# 1__STLU01.net
KiCad netlist of a schematic drawn in Altium Designer
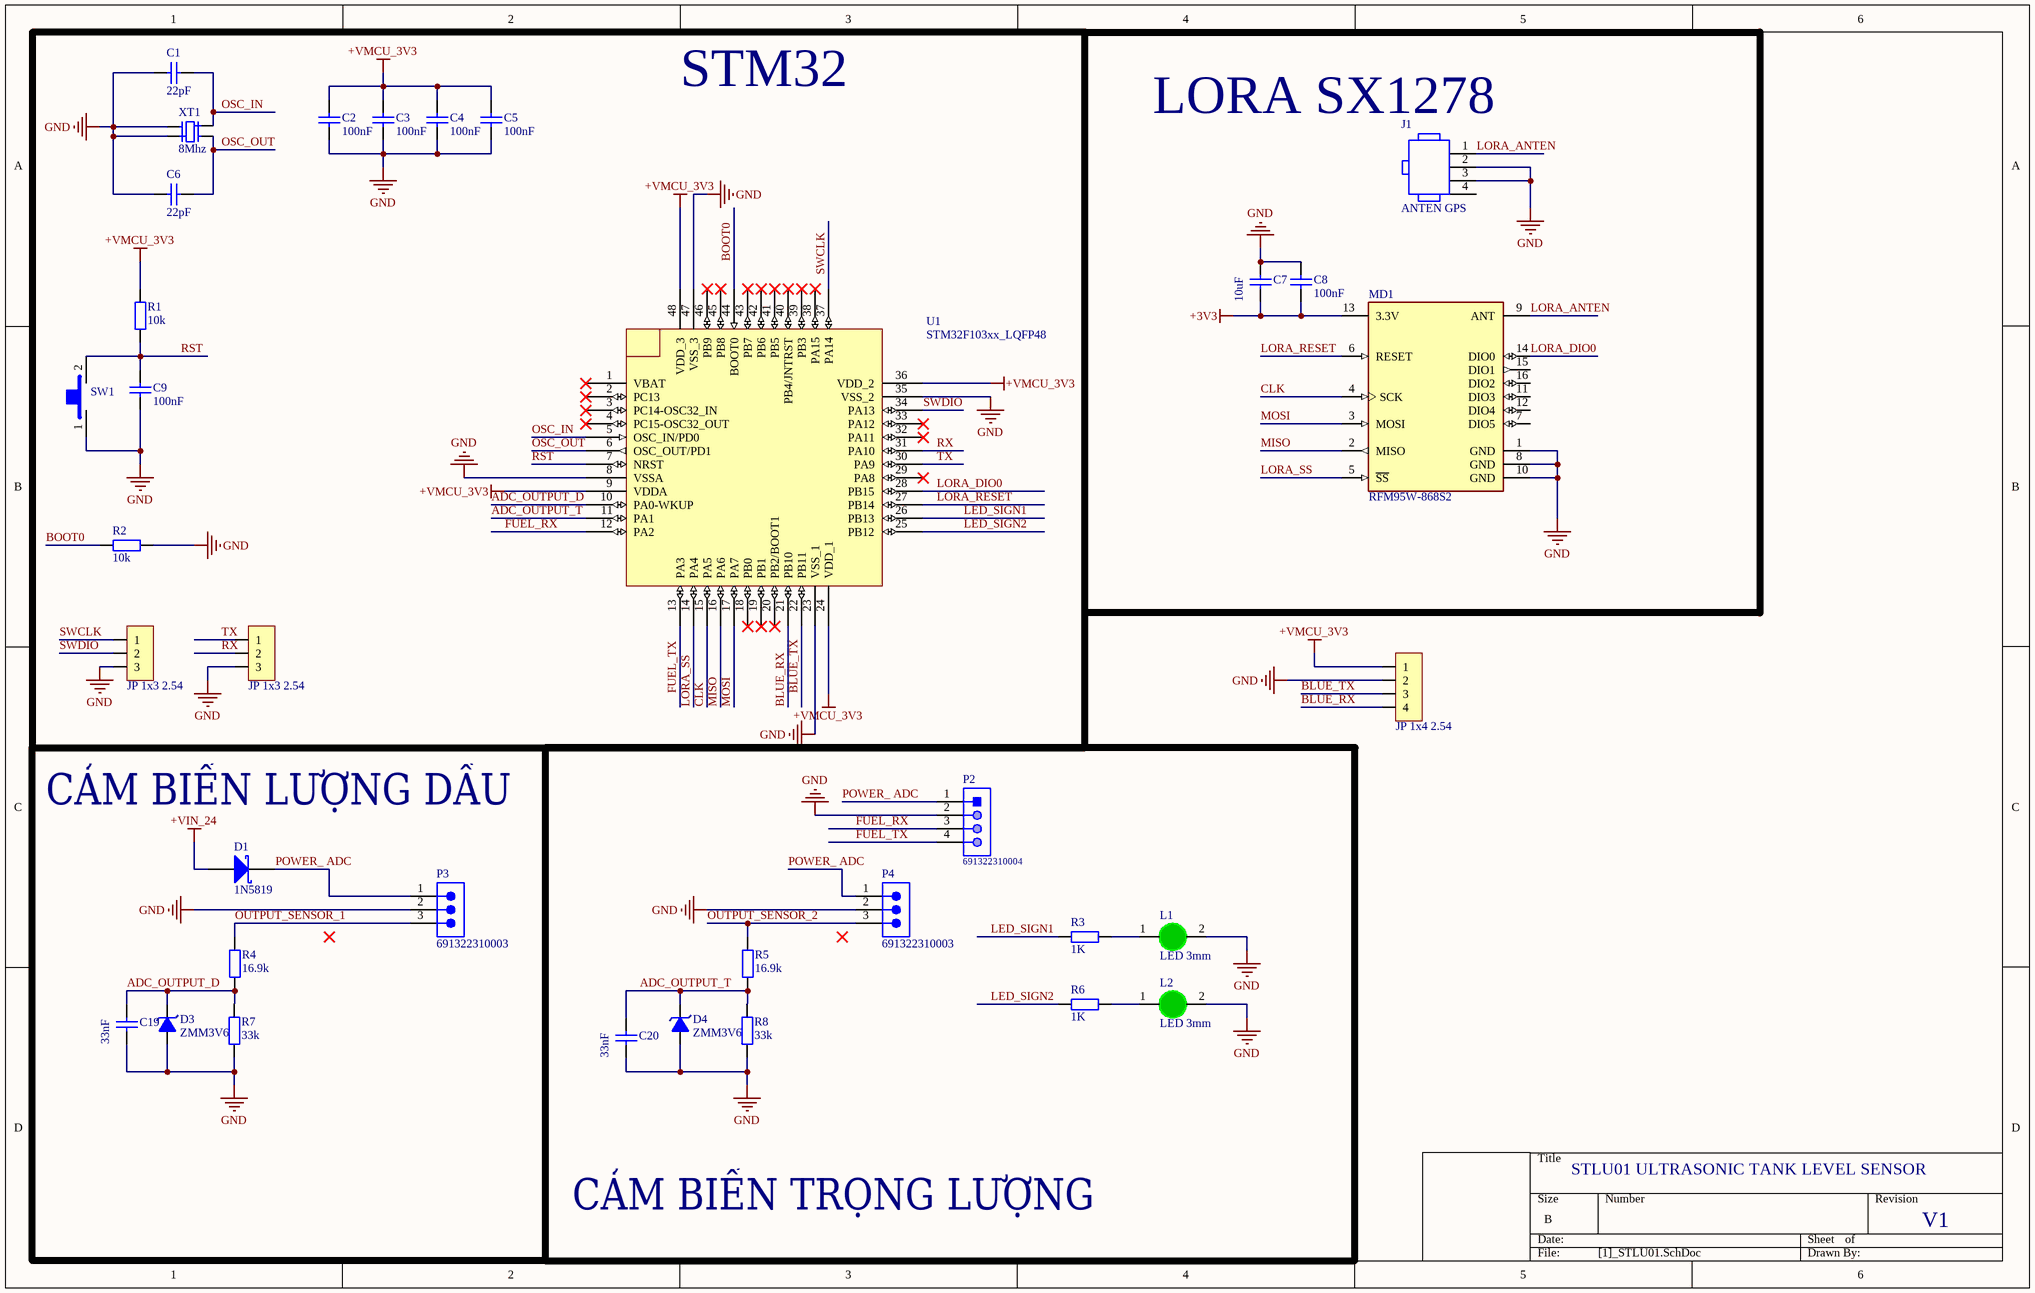
[diagram p0: [1]_STLU01.SchDoc]

(export (version "E")
  (design (tool "Eeschema 10.0.6"))
  (components
    (comp (ref "C1")
      (value "22pF")
      (footprint "tu 0603")
      (description "Dán")
      (libsource (lib "Altium_Lib_by_KhueNguyenCreator") (part "Tu 0603 101 50V 10%"))
    )
    (comp (ref "C2")
      (value "100nF")
      (footprint "tu 0603")
      (description "Dán")
      (libsource (lib "Altium_Lib_by_KhueNguyenCreator") (part "Tu 0603 104 50V 10%"))
    )
    (comp (ref "C3")
      (value "100nF")
      (footprint "tu 0603")
      (description "Dán")
      (libsource (lib "Altium_Lib_by_KhueNguyenCreator") (part "Tu 0603 104 50V 10%"))
    )
    (comp (ref "C4")
      (value "100nF")
      (footprint "tu 0603")
      (description "Dán")
      (libsource (lib "Altium_Lib_by_KhueNguyenCreator") (part "Tu 0603 104 50V 10%"))
    )
    (comp (ref "C5")
      (value "100nF")
      (footprint "tu 0603")
      (description "Dán")
      (libsource (lib "Altium_Lib_by_KhueNguyenCreator") (part "Tu 0603 104 50V 10%"))
    )
    (comp (ref "C6")
      (value "22pF")
      (footprint "tu 0603")
      (description "Dán")
      (libsource (lib "Altium_Lib_by_KhueNguyenCreator") (part "Tu 0603 101 50V 10%"))
    )
    (comp (ref "C7")
      (value "10uF")
      (footprint "tu 0603")
      (description "Dán")
      (libsource (lib "Altium_Lib_by_KhueNguyenCreator") (part "Tu 0603 105 16V 20%"))
    )
    (comp (ref "C8")
      (value "100nF")
      (footprint "tu 0603")
      (description "Dán")
      (libsource (lib "Altium_Lib_by_KhueNguyenCreator") (part "Tu 0603 104 50V 10%"))
    )
    (comp (ref "C9")
      (value "100nF")
      (footprint "tu 0603")
      (description "Dán")
      (libsource (lib "Altium_Lib_by_KhueNguyenCreator") (part "Tu 0603 105 50V 10%"))
    )
    (comp (ref "C19")
      (value "33nF")
      (footprint "tu 0603")
      (description "Dán")
      (libsource (lib "Altium_Lib_by_KhueNguyenCreator") (part "Tu 0603 105 16V 20%"))
    )
    (comp (ref "C20")
      (value "33nF")
      (footprint "tu 0603")
      (description "Dán")
      (libsource (lib "Altium_Lib_by_KhueNguyenCreator") (part "Tu 0603 105 16V 20%"))
    )
    (comp (ref "D1")
      (value "1N5819")
      (footprint "DO-214AA")
      (description "DIODE SCHOTTKY 1A 40V SMA DO-214AA")
      (fields (field (name "MANUFACTURER") "Fairchild") (field (name "PART NUMBER") "SS14"))
      (libsource (lib "COMPONENT_INS") (part "DIO_SS14"))
    )
    (comp (ref "D3")
      (value "ZMM3V6")
      (footprint "SOD_80")
      (description "ZMM3V6 3.6V 500mW SMD SOD-80")
      (fields (field (name "MANUFACTURER") "On Semiconductor"))
      (libsource (lib "COMPONENT_INS") (part "DIO_ZMM3V6"))
    )
    (comp (ref "D4")
      (value "ZMM3V6")
      (footprint "SOD_80")
      (description "ZMM3V6 3.6V 500mW SMD SOD-80")
      (fields (field (name "MANUFACTURER") "On Semiconductor"))
      (libsource (lib "COMPONENT_INS") (part "DIO_ZMM3V6"))
    )
    (comp (ref "J1")
      (value "ANTEN GPS")
      (footprint "TG-RECE-20369-001E-4_V")
      (description "RF Connector, Onboard Receptacle, IPEX MHFIII")
      (fields (field (name "MANUFACTURER") "Taoglas") (field (name "PARTNUMBER") "RECE-20369-001E-01"))
      (libsource (lib "Altium Content Vault") (part "TG-RECE-20369-001E-01-4"))
    )
    (comp (ref "JP1")
      (value "JP 1x3 2.54")
      (footprint "JP 1x3 DT")
      (description "Cắm")
      (libsource (lib "Altium_Lib_by_KhueNguyenCreator") (part "JP 1x3 2.54 Duc Thang"))
    )
    (comp (ref "JP2")
      (value "JP 1x3 2.54")
      (footprint "JP 1x3 DT")
      (description "Cắm")
      (libsource (lib "Altium_Lib_by_KhueNguyenCreator") (part "JP 1x3 2.54 Duc Thang"))
    )
    (comp (ref "JP3")
      (value "JP 1x4 2.54")
      (footprint "JP 1x4 DT")
      (description "Cắm")
      (libsource (lib "Altium_Lib_by_KhueNguyenCreator") (part "JP 1x4 2.54 Duc Thang"))
    )
    (comp (ref "L1")
      (value "LED 3mm")
      (footprint "LED-3MM-GREEN")
      (description "Cắm")
      (libsource (lib "Altium_Lib_by_KhueNguyenCreator") (part "LED 3mm Xanh La"))
    )
    (comp (ref "L2")
      (value "LED 3mm")
      (footprint "LED-3MM-GREEN")
      (description "Cắm")
      (libsource (lib "Altium_Lib_by_KhueNguyenCreator") (part "LED 3mm Xanh La"))
    )
    (comp (ref "MD1")
      (value "RFM95W-868S2")
      (footprint "FP-RFM95W-868S2-MFG")
      (description "RX TXRX MODULE ISM < 1GHZ SMD")
      (libsource (lib "Altium Content Vault") (part "17626aa6fba47fab2b206b7c140802e"))
    )
    (comp (ref "P2")
      (value "691322310004")
      (footprint "691322310004")
      (description "Serie 322 - 3.81mm Horizontal PCB Header WR-TBL, 4 pin")
      (fields (field (name "MANUFACTURER") "Wurth Elektronik") (field (name "PUBLISHER") "WurthElektronik"))
      (libsource (lib "Altium Content Vault") (part "WE-CN-1P-M-R4"))
    )
    (comp (ref "P3")
      (value "691322310003")
      (footprint "691322310003")
      (fields (field (name "VOLTAGE") "300V"))
      (libsource (lib "Altium Content Vault") (part "TBL - 1R - 03P - Male"))
    )
    (comp (ref "P4")
      (value "691322310003")
      (footprint "691322310003")
      (fields (field (name "VOLTAGE") "300V"))
      (libsource (lib "Altium Content Vault") (part "TBL - 1R - 03P - Male"))
    )
    (comp (ref "R1")
      (value "10k")
      (footprint "tro smd 0603")
      (description "Dán")
      (libsource (lib "Altium_Lib_by_KhueNguyenCreator") (part "Tro 0603 5% 10k"))
    )
    (comp (ref "R2")
      (value "10k")
      (footprint "tro smd 0603")
      (description "Dán")
      (libsource (lib "Altium_Lib_by_KhueNguyenCreator") (part "Tro 0603 5% 10k"))
    )
    (comp (ref "R3")
      (value "1K")
      (footprint "tro smd 0805")
      (description "Dán")
      (libsource (lib "Altium_Lib_by_KhueNguyenCreator") (part "Tro 0805 5% 1k"))
    )
    (comp (ref "R4")
      (value "16.9k")
      (footprint "tro smd 0805")
      (description "Dán")
      (libsource (lib "Altium_Lib_by_KhueNguyenCreator") (part "Tro 0805 5% 1k"))
    )
    (comp (ref "R5")
      (value "16.9k")
      (footprint "tro smd 0805")
      (description "Dán")
      (libsource (lib "Altium_Lib_by_KhueNguyenCreator") (part "Tro 0805 5% 1k"))
    )
    (comp (ref "R6")
      (value "1K")
      (footprint "tro smd 0805")
      (description "Dán")
      (libsource (lib "Altium_Lib_by_KhueNguyenCreator") (part "Tro 0805 5% 1k"))
    )
    (comp (ref "R7")
      (value "33k")
      (footprint "tro smd 0805")
      (description "Dán")
      (libsource (lib "Altium_Lib_by_KhueNguyenCreator") (part "Tro 0805 5% 1k"))
    )
    (comp (ref "R8")
      (value "33k")
      (footprint "tro smd 0805")
      (description "Dán")
      (libsource (lib "Altium_Lib_by_KhueNguyenCreator") (part "Tro 0805 5% 1k"))
    )
    (comp (ref "SW1")
      (value "Tactile")
      (footprint "SW 2P SMD")
      (description "SMD Mini Push Button Switch 2 Pin 3x6x2.7mm")
      (fields (field (name "MANUFACTURER") "OEM") (field (name "PART NUMBER") "SPST 2 PIN SMD"))
      (libsource (lib "COMPONENT_INS") (part "SW_SPDT_2PIN"))
    )
    (comp (ref "U1")
      (value "STM32F103xx_LQFP48")
      (footprint "STM32_LQPF48")
      (fields (field (name "PUBLISHER") "Altium Limited"))
      (libsource (lib "Altium_Lib_by_KhueNguyenCreator") (part "STM32F103xx_LQFP48"))
    )
    (comp (ref "XT1")
      (value "8Mhz")
      (footprint "Thach Anh 4 chan 1")
      (description "Crystal For all Crystal 2pin.")
      (libsource (lib "Altium_Lib_by_KhueNguyenCreator") (part "Thach Anh 4 Chan SMD"))
    )
  )
  (nets
    (net (code "1") (name "+3V3") (class "Default")
      (node (ref "C7") (pin "2") (pinfunction "2_2") (pintype "passive"))
      (node (ref "C8") (pin "2") (pinfunction "2_2") (pintype "passive"))
      (node (ref "MD1") (pin "13") (pinfunction "3.3V_13") (pintype "power_in"))
    )
    (net (code "2") (name "+VIN_24") (class "Default")
      (node (ref "D1") (pin "1") (pinfunction "A_1") (pintype "passive"))
    )
    (net (code "3") (name "+VMCU_3V3") (class "Default")
      (node (ref "C2") (pin "1") (pinfunction "1_1") (pintype "passive"))
      (node (ref "C3") (pin "1") (pinfunction "1_1") (pintype "passive"))
      (node (ref "C4") (pin "1") (pinfunction "1_1") (pintype "passive"))
      (node (ref "C5") (pin "1") (pinfunction "1_1") (pintype "passive"))
      (node (ref "JP3") (pin "1") (pinfunction "1_1") (pintype "passive"))
      (node (ref "R1") (pin "2") (pinfunction "2_2") (pintype "passive"))
      (node (ref "U1") (pin "24") (pinfunction "VDD_1_24") (pintype "power_in"))
      (node (ref "U1") (pin "36") (pinfunction "VDD_2_36") (pintype "power_in"))
      (node (ref "U1") (pin "48") (pinfunction "VDD_3_48") (pintype "power_in"))
      (node (ref "U1") (pin "9") (pinfunction "VDDA_9") (pintype "power_in"))
    )
    (net (code "4") (name "/ADC_OUTPUT_D") (class "Default")
      (node (ref "C19") (pin "1") (pinfunction "1_1") (pintype "passive"))
      (node (ref "D3") (pin "2") (pinfunction "K_2") (pintype "passive"))
      (node (ref "R4") (pin "1") (pinfunction "1_1") (pintype "passive"))
      (node (ref "R7") (pin "2") (pinfunction "2_2") (pintype "passive"))
      (node (ref "U1") (pin "10") (pinfunction "PA0-WKUP_10") (pintype "bidirectional"))
    )
    (net (code "5") (name "/ADC_OUTPUT_T") (class "Default")
      (node (ref "C20") (pin "1") (pinfunction "1_1") (pintype "passive"))
      (node (ref "D4") (pin "2") (pinfunction "K_2") (pintype "passive"))
      (node (ref "R5") (pin "1") (pinfunction "1_1") (pintype "passive"))
      (node (ref "R8") (pin "2") (pinfunction "2_2") (pintype "passive"))
      (node (ref "U1") (pin "11") (pinfunction "PA1_11") (pintype "bidirectional"))
    )
    (net (code "6") (name "/BLUE_RX") (class "Default")
      (node (ref "JP3") (pin "4") (pinfunction "4_4") (pintype "passive"))
      (node (ref "U1") (pin "21") (pinfunction "PB10_21") (pintype "bidirectional"))
    )
    (net (code "7") (name "/BLUE_TX") (class "Default")
      (node (ref "JP3") (pin "3") (pinfunction "3_3") (pintype "passive"))
      (node (ref "U1") (pin "22") (pinfunction "PB11_22") (pintype "bidirectional"))
    )
    (net (code "8") (name "/BOOT0") (class "Default")
      (node (ref "R2") (pin "2") (pinfunction "2_2") (pintype "passive"))
      (node (ref "U1") (pin "44") (pinfunction "BOOT0_44") (pintype "input"))
    )
    (net (code "9") (name "/CLK") (class "Default")
      (node (ref "MD1") (pin "4") (pinfunction "SCK_4") (pintype "input"))
      (node (ref "U1") (pin "15") (pinfunction "PA5_15") (pintype "bidirectional"))
    )
    (net (code "10") (name "/FUEL_RX") (class "Default")
      (node (ref "P2") (pin "3") (pinfunction "3_3") (pintype "passive"))
      (node (ref "U1") (pin "12") (pinfunction "PA2_12") (pintype "bidirectional"))
    )
    (net (code "11") (name "/FUEL_TX") (class "Default")
      (node (ref "P2") (pin "4") (pinfunction "4_4") (pintype "passive"))
      (node (ref "U1") (pin "13") (pinfunction "PA3_13") (pintype "bidirectional"))
    )
    (net (code "12") (name "/LED_SIGN1") (class "Default")
      (node (ref "R3") (pin "2") (pinfunction "2_2") (pintype "passive"))
      (node (ref "U1") (pin "26") (pinfunction "PB13_26") (pintype "bidirectional"))
    )
    (net (code "13") (name "/LED_SIGN2") (class "Default")
      (node (ref "R6") (pin "2") (pinfunction "2_2") (pintype "passive"))
      (node (ref "U1") (pin "25") (pinfunction "PB12_25") (pintype "bidirectional"))
    )
    (net (code "14") (name "/LORA_ANTEN") (class "Default")
      (node (ref "J1") (pin "1") (pinfunction "1_1") (pintype "passive"))
      (node (ref "MD1") (pin "9") (pinfunction "ANT_9") (pintype "passive"))
    )
    (net (code "15") (name "/LORA_DIO0") (class "Default")
      (node (ref "MD1") (pin "14") (pinfunction "DIO0_14") (pintype "bidirectional"))
      (node (ref "U1") (pin "28") (pinfunction "PB15_28") (pintype "bidirectional"))
    )
    (net (code "16") (name "/LORA_RESET") (class "Default")
      (node (ref "MD1") (pin "6") (pinfunction "RESET_6") (pintype "input"))
      (node (ref "U1") (pin "27") (pinfunction "PB14_27") (pintype "bidirectional"))
    )
    (net (code "17") (name "/LORA_SS") (class "Default")
      (node (ref "MD1") (pin "5") (pinfunction "~{SS}_5") (pintype "input"))
      (node (ref "U1") (pin "14") (pinfunction "PA4_14") (pintype "bidirectional"))
    )
    (net (code "18") (name "/MISO") (class "Default")
      (node (ref "MD1") (pin "2") (pinfunction "MISO_2") (pintype "output"))
      (node (ref "U1") (pin "16") (pinfunction "PA6_16") (pintype "bidirectional"))
    )
    (net (code "19") (name "/MOSI") (class "Default")
      (node (ref "MD1") (pin "3") (pinfunction "MOSI_3") (pintype "input"))
      (node (ref "U1") (pin "17") (pinfunction "PA7_17") (pintype "bidirectional"))
    )
    (net (code "20") (name "/OSC_IN") (class "Default")
      (node (ref "C1") (pin "1") (pinfunction "1_1") (pintype "passive"))
      (node (ref "U1") (pin "5") (pinfunction "OSC_IN/PD0_5") (pintype "input"))
      (node (ref "XT1") (pin "3") (pinfunction "3_3") (pintype "passive"))
    )
    (net (code "21") (name "/OSC_OUT") (class "Default")
      (node (ref "C6") (pin "1") (pinfunction "1_1") (pintype "passive"))
      (node (ref "U1") (pin "6") (pinfunction "OSC_OUT/PD1_6") (pintype "output"))
      (node (ref "XT1") (pin "1") (pinfunction "1_1") (pintype "passive"))
    )
    (net (code "22") (name "/OUTPUT_SENSOR_1") (class "Default")
      (node (ref "P3") (pin "3") (pinfunction "3_3") (pintype "passive"))
      (node (ref "R4") (pin "2") (pinfunction "2_2") (pintype "passive"))
    )
    (net (code "23") (name "/OUTPUT_SENSOR_2") (class "Default")
      (node (ref "P4") (pin "3") (pinfunction "3_3") (pintype "passive"))
      (node (ref "R5") (pin "2") (pinfunction "2_2") (pintype "passive"))
    )
    (net (code "24") (name "/POWER_ ADC") (class "Default")
      (node (ref "D1") (pin "2") (pinfunction "K_2") (pintype "passive"))
      (node (ref "P2") (pin "1") (pinfunction "1_1") (pintype "passive"))
      (node (ref "P3") (pin "1") (pinfunction "1_1") (pintype "passive"))
      (node (ref "P4") (pin "1") (pinfunction "1_1") (pintype "passive"))
    )
    (net (code "25") (name "/RST") (class "Default")
      (node (ref "C9") (pin "1") (pinfunction "1_1") (pintype "passive"))
      (node (ref "R1") (pin "1") (pinfunction "1_1") (pintype "passive"))
      (node (ref "SW1") (pin "2") (pinfunction "2_2") (pintype "passive"))
      (node (ref "U1") (pin "7") (pinfunction "NRST_7") (pintype "bidirectional"))
    )
    (net (code "26") (name "/RX") (class "Default")
      (node (ref "JP2") (pin "2") (pinfunction "2_2") (pintype "passive"))
      (node (ref "U1") (pin "31") (pinfunction "PA10_31") (pintype "bidirectional"))
    )
    (net (code "27") (name "/SWCLK") (class "Default")
      (node (ref "JP1") (pin "1") (pinfunction "1_1") (pintype "passive"))
      (node (ref "U1") (pin "37") (pinfunction "PA14_37") (pintype "bidirectional"))
    )
    (net (code "28") (name "/SWDIO") (class "Default")
      (node (ref "JP1") (pin "2") (pinfunction "2_2") (pintype "passive"))
      (node (ref "U1") (pin "34") (pinfunction "PA13_34") (pintype "bidirectional"))
    )
    (net (code "29") (name "/TX") (class "Default")
      (node (ref "JP2") (pin "1") (pinfunction "1_1") (pintype "passive"))
      (node (ref "U1") (pin "30") (pinfunction "PA9_30") (pintype "bidirectional"))
    )
    (net (code "30") (name "GND") (class "Default")
      (node (ref "C1") (pin "2") (pinfunction "2_2") (pintype "passive"))
      (node (ref "C19") (pin "2") (pinfunction "2_2") (pintype "passive"))
      (node (ref "C2") (pin "2") (pinfunction "2_2") (pintype "passive"))
      (node (ref "C20") (pin "2") (pinfunction "2_2") (pintype "passive"))
      (node (ref "C3") (pin "2") (pinfunction "2_2") (pintype "passive"))
      (node (ref "C4") (pin "2") (pinfunction "2_2") (pintype "passive"))
      (node (ref "C5") (pin "2") (pinfunction "2_2") (pintype "passive"))
      (node (ref "C6") (pin "2") (pinfunction "2_2") (pintype "passive"))
      (node (ref "C7") (pin "1") (pinfunction "1_1") (pintype "passive"))
      (node (ref "C8") (pin "1") (pinfunction "1_1") (pintype "passive"))
      (node (ref "C9") (pin "2") (pinfunction "2_2") (pintype "passive"))
      (node (ref "D3") (pin "1") (pinfunction "A_1") (pintype "passive"))
      (node (ref "D4") (pin "1") (pinfunction "A_1") (pintype "passive"))
      (node (ref "J1") (pin "2") (pinfunction "2_2") (pintype "passive"))
      (node (ref "J1") (pin "3") (pinfunction "3_3") (pintype "passive"))
      (node (ref "JP1") (pin "3") (pinfunction "3_3") (pintype "passive"))
      (node (ref "JP2") (pin "3") (pinfunction "3_3") (pintype "passive"))
      (node (ref "JP3") (pin "2") (pinfunction "2_2") (pintype "passive"))
      (node (ref "L1") (pin "2") (pinfunction "K_2") (pintype "passive"))
      (node (ref "L2") (pin "2") (pinfunction "K_2") (pintype "passive"))
      (node (ref "MD1") (pin "1") (pinfunction "GND_1") (pintype "power_in"))
      (node (ref "MD1") (pin "10") (pinfunction "GND_10") (pintype "power_in"))
      (node (ref "MD1") (pin "8") (pinfunction "GND_8") (pintype "power_in"))
      (node (ref "P2") (pin "2") (pinfunction "2_2") (pintype "passive"))
      (node (ref "P3") (pin "2") (pinfunction "2_2") (pintype "passive"))
      (node (ref "P4") (pin "2") (pinfunction "2_2") (pintype "passive"))
      (node (ref "R2") (pin "1") (pinfunction "1_1") (pintype "passive"))
      (node (ref "R7") (pin "1") (pinfunction "1_1") (pintype "passive"))
      (node (ref "R8") (pin "1") (pinfunction "1_1") (pintype "passive"))
      (node (ref "SW1") (pin "1") (pinfunction "1_1") (pintype "passive"))
      (node (ref "U1") (pin "23") (pinfunction "VSS_1_23") (pintype "power_in"))
      (node (ref "U1") (pin "35") (pinfunction "VSS_2_35") (pintype "power_in"))
      (node (ref "U1") (pin "47") (pinfunction "VSS_3_47") (pintype "power_in"))
      (node (ref "U1") (pin "8") (pinfunction "VSSA_8") (pintype "power_in"))
      (node (ref "XT1") (pin "2") (pinfunction "2_2") (pintype "passive"))
      (node (ref "XT1") (pin "4") (pinfunction "4_4") (pintype "passive"))
    )
    (net (code "31") (name "Net-(L1-A)") (class "Default")
      (node (ref "L1") (pin "1") (pinfunction "A_1") (pintype "passive"))
      (node (ref "R3") (pin "1") (pinfunction "1_1") (pintype "passive"))
    )
    (net (code "32") (name "Net-(L2-A)") (class "Default")
      (node (ref "L2") (pin "1") (pinfunction "A_1") (pintype "passive"))
      (node (ref "R6") (pin "1") (pinfunction "1_1") (pintype "passive"))
    )
    (net (code "33") (name "unconnected-(J1-Pad4)") (class "Default")
      (node (ref "J1") (pin "4") (pinfunction "4_4") (pintype "passive"))
    )
    (net (code "34") (name "unconnected-(MD1-DIO1-Pad15)") (class "Default")
      (node (ref "MD1") (pin "15") (pinfunction "DIO1_15") (pintype "output"))
    )
    (net (code "35") (name "unconnected-(MD1-DIO2-Pad16)") (class "Default")
      (node (ref "MD1") (pin "16") (pinfunction "DIO2_16") (pintype "bidirectional"))
    )
    (net (code "36") (name "unconnected-(MD1-DIO3-Pad11)") (class "Default")
      (node (ref "MD1") (pin "11") (pinfunction "DIO3_11") (pintype "bidirectional"))
    )
    (net (code "37") (name "unconnected-(MD1-DIO4-Pad12)") (class "Default")
      (node (ref "MD1") (pin "12") (pinfunction "DIO4_12") (pintype "bidirectional"))
    )
    (net (code "38") (name "unconnected-(MD1-DIO5-Pad7)") (class "Default")
      (node (ref "MD1") (pin "7") (pinfunction "DIO5_7") (pintype "bidirectional"))
    )
    (net (code "39") (name "unconnected-(U1-PA8-Pad29)") (class "Default")
      (node (ref "U1") (pin "29") (pinfunction "PA8_29") (pintype "bidirectional+no_connect"))
    )
    (net (code "40") (name "unconnected-(U1-PA11-Pad32)") (class "Default")
      (node (ref "U1") (pin "32") (pinfunction "PA11_32") (pintype "bidirectional+no_connect"))
    )
    (net (code "41") (name "unconnected-(U1-PA12-Pad33)") (class "Default")
      (node (ref "U1") (pin "33") (pinfunction "PA12_33") (pintype "bidirectional+no_connect"))
    )
    (net (code "42") (name "unconnected-(U1-PA15-Pad38)") (class "Default")
      (node (ref "U1") (pin "38") (pinfunction "PA15_38") (pintype "bidirectional+no_connect"))
    )
    (net (code "43") (name "unconnected-(U1-PB0-Pad18)") (class "Default")
      (node (ref "U1") (pin "18") (pinfunction "PB0_18") (pintype "bidirectional+no_connect"))
    )
    (net (code "44") (name "unconnected-(U1-PB1-Pad19)") (class "Default")
      (node (ref "U1") (pin "19") (pinfunction "PB1_19") (pintype "bidirectional+no_connect"))
    )
    (net (code "45") (name "unconnected-(U1-PB2{slash}BOOT1-Pad20)") (class "Default")
      (node (ref "U1") (pin "20") (pinfunction "PB2/BOOT1_20") (pintype "bidirectional+no_connect"))
    )
    (net (code "46") (name "unconnected-(U1-PB3-Pad39)") (class "Default")
      (node (ref "U1") (pin "39") (pinfunction "PB3_39") (pintype "bidirectional+no_connect"))
    )
    (net (code "47") (name "unconnected-(U1-PB4{slash}JNTRST-Pad40)") (class "Default")
      (node (ref "U1") (pin "40") (pinfunction "PB4/JNTRST_40") (pintype "bidirectional+no_connect"))
    )
    (net (code "48") (name "unconnected-(U1-PB5-Pad41)") (class "Default")
      (node (ref "U1") (pin "41") (pinfunction "PB5_41") (pintype "bidirectional+no_connect"))
    )
    (net (code "49") (name "unconnected-(U1-PB6-Pad42)") (class "Default")
      (node (ref "U1") (pin "42") (pinfunction "PB6_42") (pintype "bidirectional+no_connect"))
    )
    (net (code "50") (name "unconnected-(U1-PB7-Pad43)") (class "Default")
      (node (ref "U1") (pin "43") (pinfunction "PB7_43") (pintype "bidirectional+no_connect"))
    )
    (net (code "51") (name "unconnected-(U1-PB8-Pad45)") (class "Default")
      (node (ref "U1") (pin "45") (pinfunction "PB8_45") (pintype "bidirectional+no_connect"))
    )
    (net (code "52") (name "unconnected-(U1-PB9-Pad46)") (class "Default")
      (node (ref "U1") (pin "46") (pinfunction "PB9_46") (pintype "bidirectional+no_connect"))
    )
    (net (code "53") (name "unconnected-(U1-PC13-Pad2)") (class "Default")
      (node (ref "U1") (pin "2") (pinfunction "PC13_2") (pintype "bidirectional+no_connect"))
    )
    (net (code "54") (name "unconnected-(U1-PC14-OSC32_IN-Pad3)") (class "Default")
      (node (ref "U1") (pin "3") (pinfunction "PC14-OSC32_IN_3") (pintype "bidirectional+no_connect"))
    )
    (net (code "55") (name "unconnected-(U1-PC15-OSC32_OUT-Pad4)") (class "Default")
      (node (ref "U1") (pin "4") (pinfunction "PC15-OSC32_OUT_4") (pintype "bidirectional+no_connect"))
    )
    (net (code "56") (name "unconnected-(U1-VBAT-Pad1)") (class "Default")
      (node (ref "U1") (pin "1") (pinfunction "VBAT_1") (pintype "power_in+no_connect"))
    )
  )
)
